# BMS_BALANCE.net
KiCad netlist of a schematic drawn in Altium Designer
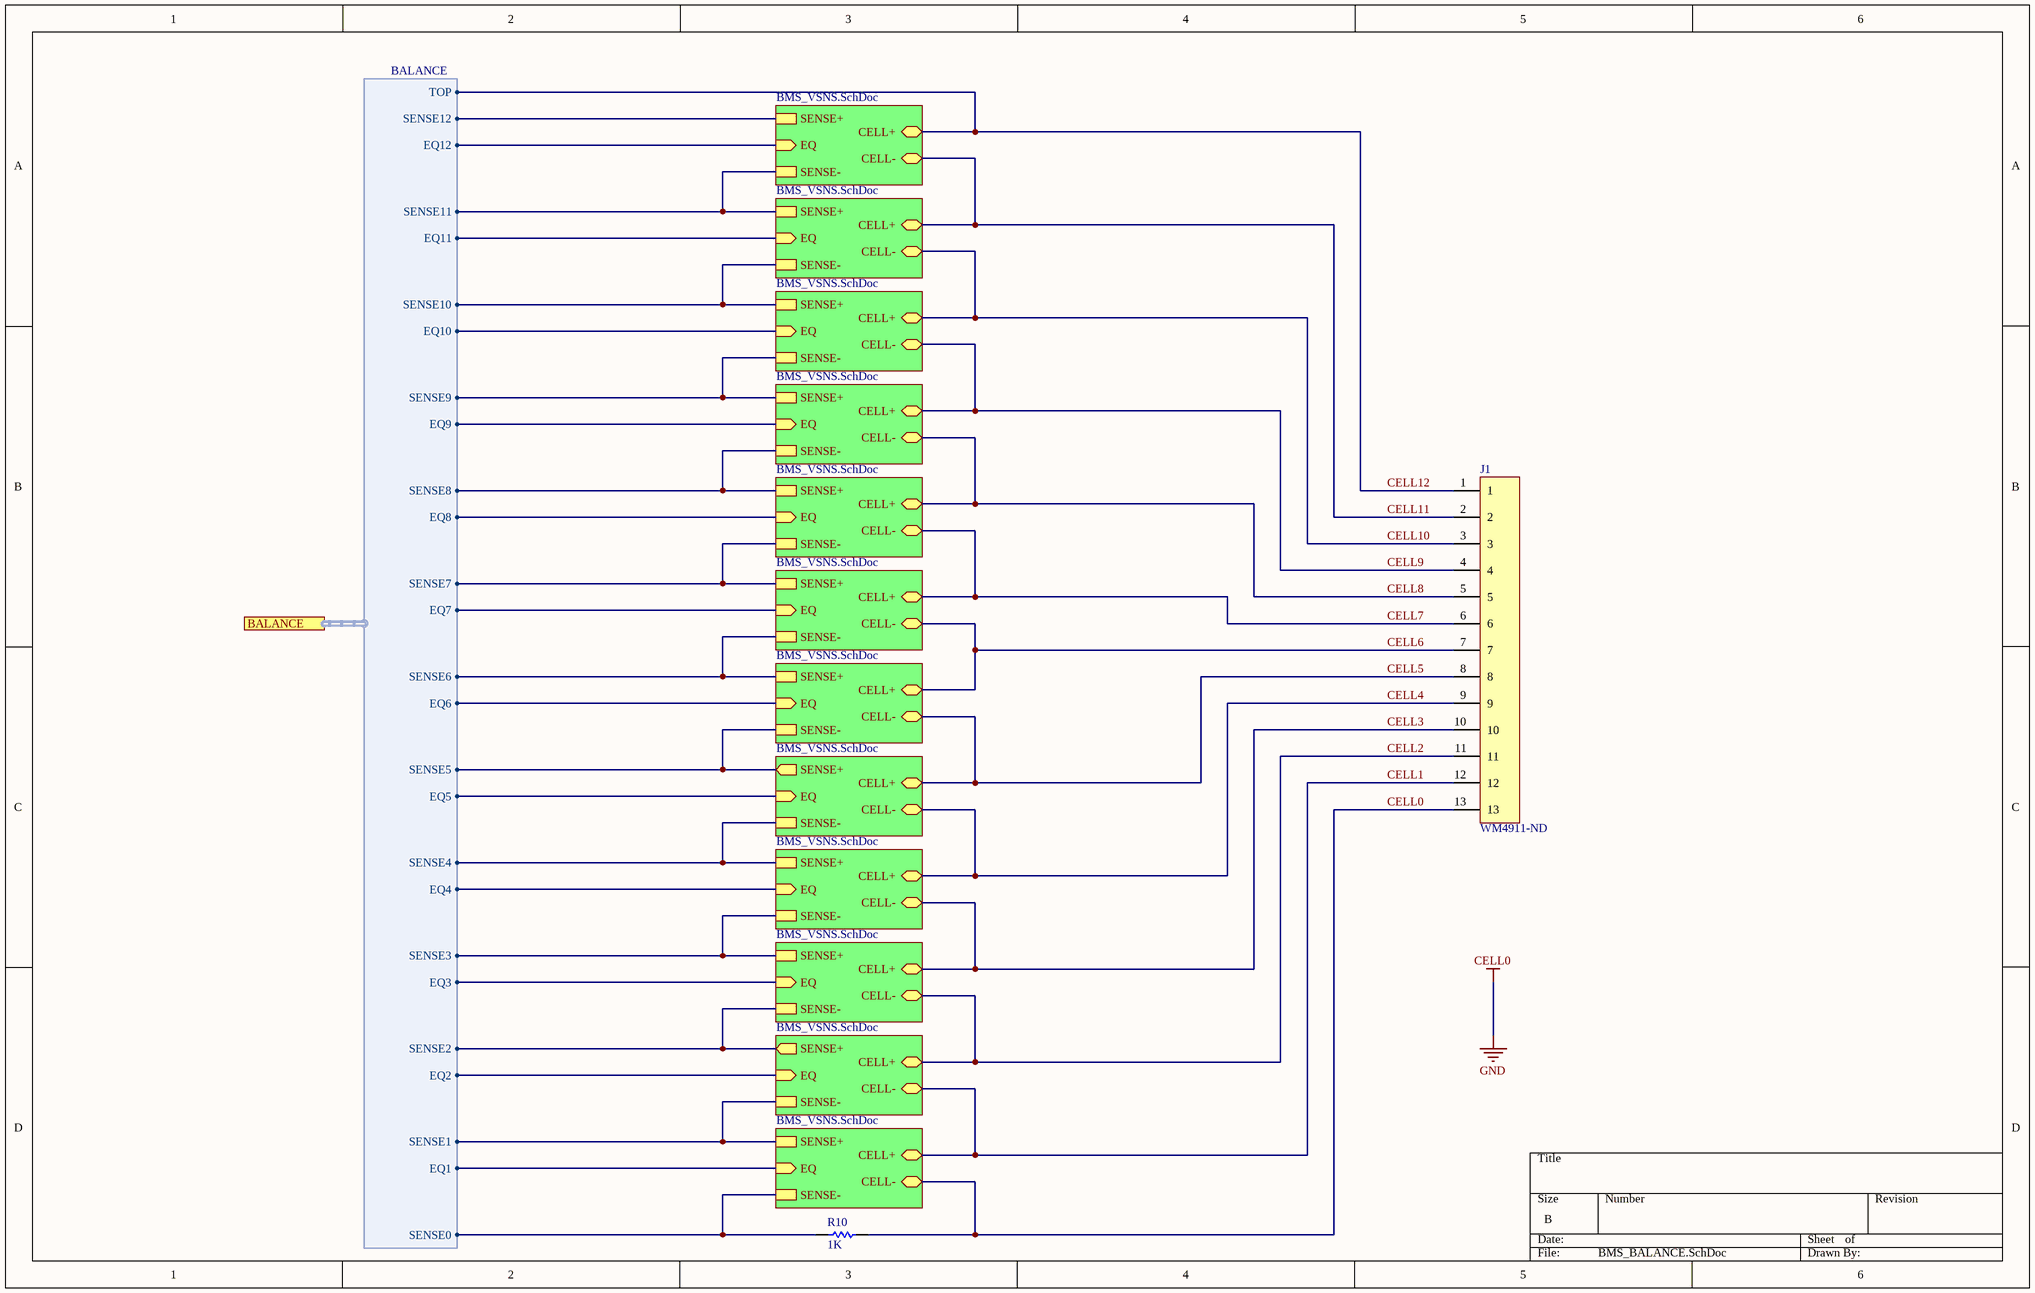
[diagram p0: BMS_BALANCE.SchDoc]

(export (version "E")
  (design (tool "Eeschema 10.0.6"))
  (components
    (comp (ref "J1")
      (value "WM4911-ND")
      (footprint "13PIN")
      (description "CONN HEADER R/A 13POS 2.54MM")
      (fields (field (name "MANUFACTURER") "Molex") (field (name "MANUFACTURER PART NUMBER") "0705530012"))
      (libsource (lib "Connectors") (part "13PIN"))
    )
    (comp (ref "R10")
      (value "1K")
      (footprint "RES-0603")
      (description "RES SMD 1K OHM 1% 1/10W 0603")
      (fields
        (field (name "MANUFACTURER") "Vishay Dale")
        (field (name "MANUFACTURER PART NUMBER") "CRCW06031K00FKEA")
      )
      (libsource (lib "Resistors") (part "0603-1KR"))
    )
  )
  (nets
    (net (code "2") (name "/CELL1") (class "Default")
      (node (ref "J1") (pin "12") (pinfunction "12_12") (pintype "passive"))
    )
    (net (code "3") (name "/CELL2") (class "Default")
      (node (ref "J1") (pin "11") (pinfunction "11_11") (pintype "passive"))
    )
    (net (code "4") (name "/CELL3") (class "Default")
      (node (ref "J1") (pin "10") (pinfunction "10_10") (pintype "passive"))
    )
    (net (code "5") (name "/CELL4") (class "Default")
      (node (ref "J1") (pin "9") (pinfunction "9_9") (pintype "passive"))
    )
    (net (code "6") (name "/CELL5") (class "Default")
      (node (ref "J1") (pin "8") (pinfunction "8_8") (pintype "passive"))
    )
    (net (code "7") (name "/CELL6") (class "Default")
      (node (ref "J1") (pin "7") (pinfunction "7_7") (pintype "passive"))
    )
    (net (code "8") (name "/CELL7") (class "Default")
      (node (ref "J1") (pin "6") (pinfunction "6_6") (pintype "passive"))
    )
    (net (code "9") (name "/CELL8") (class "Default")
      (node (ref "J1") (pin "5") (pinfunction "5_5") (pintype "passive"))
    )
    (net (code "10") (name "/CELL9") (class "Default")
      (node (ref "J1") (pin "4") (pinfunction "4_4") (pintype "passive"))
    )
    (net (code "11") (name "/CELL10") (class "Default")
      (node (ref "J1") (pin "3") (pinfunction "3_3") (pintype "passive"))
    )
    (net (code "12") (name "/CELL11") (class "Default")
      (node (ref "J1") (pin "2") (pinfunction "2_2") (pintype "passive"))
    )
    (net (code "13") (name "/CELL12") (class "Default")
      (node (ref "J1") (pin "1") (pinfunction "1_1") (pintype "passive"))
    )
    (net (code "38") (name "/SENSE-") (class "Default")
      (node (ref "R10") (pin "1") (pinfunction "1_1") (pintype "passive"))
    )
    (net (code "40") (name "CELL0") (class "Default")
      (node (ref "J1") (pin "13") (pinfunction "13_13") (pintype "passive"))
      (node (ref "R10") (pin "2") (pinfunction "2_2") (pintype "passive"))
    )
  )
)
